# 555_blinker_led.net
KiCad netlist of a schematic drawn in EasyEDA
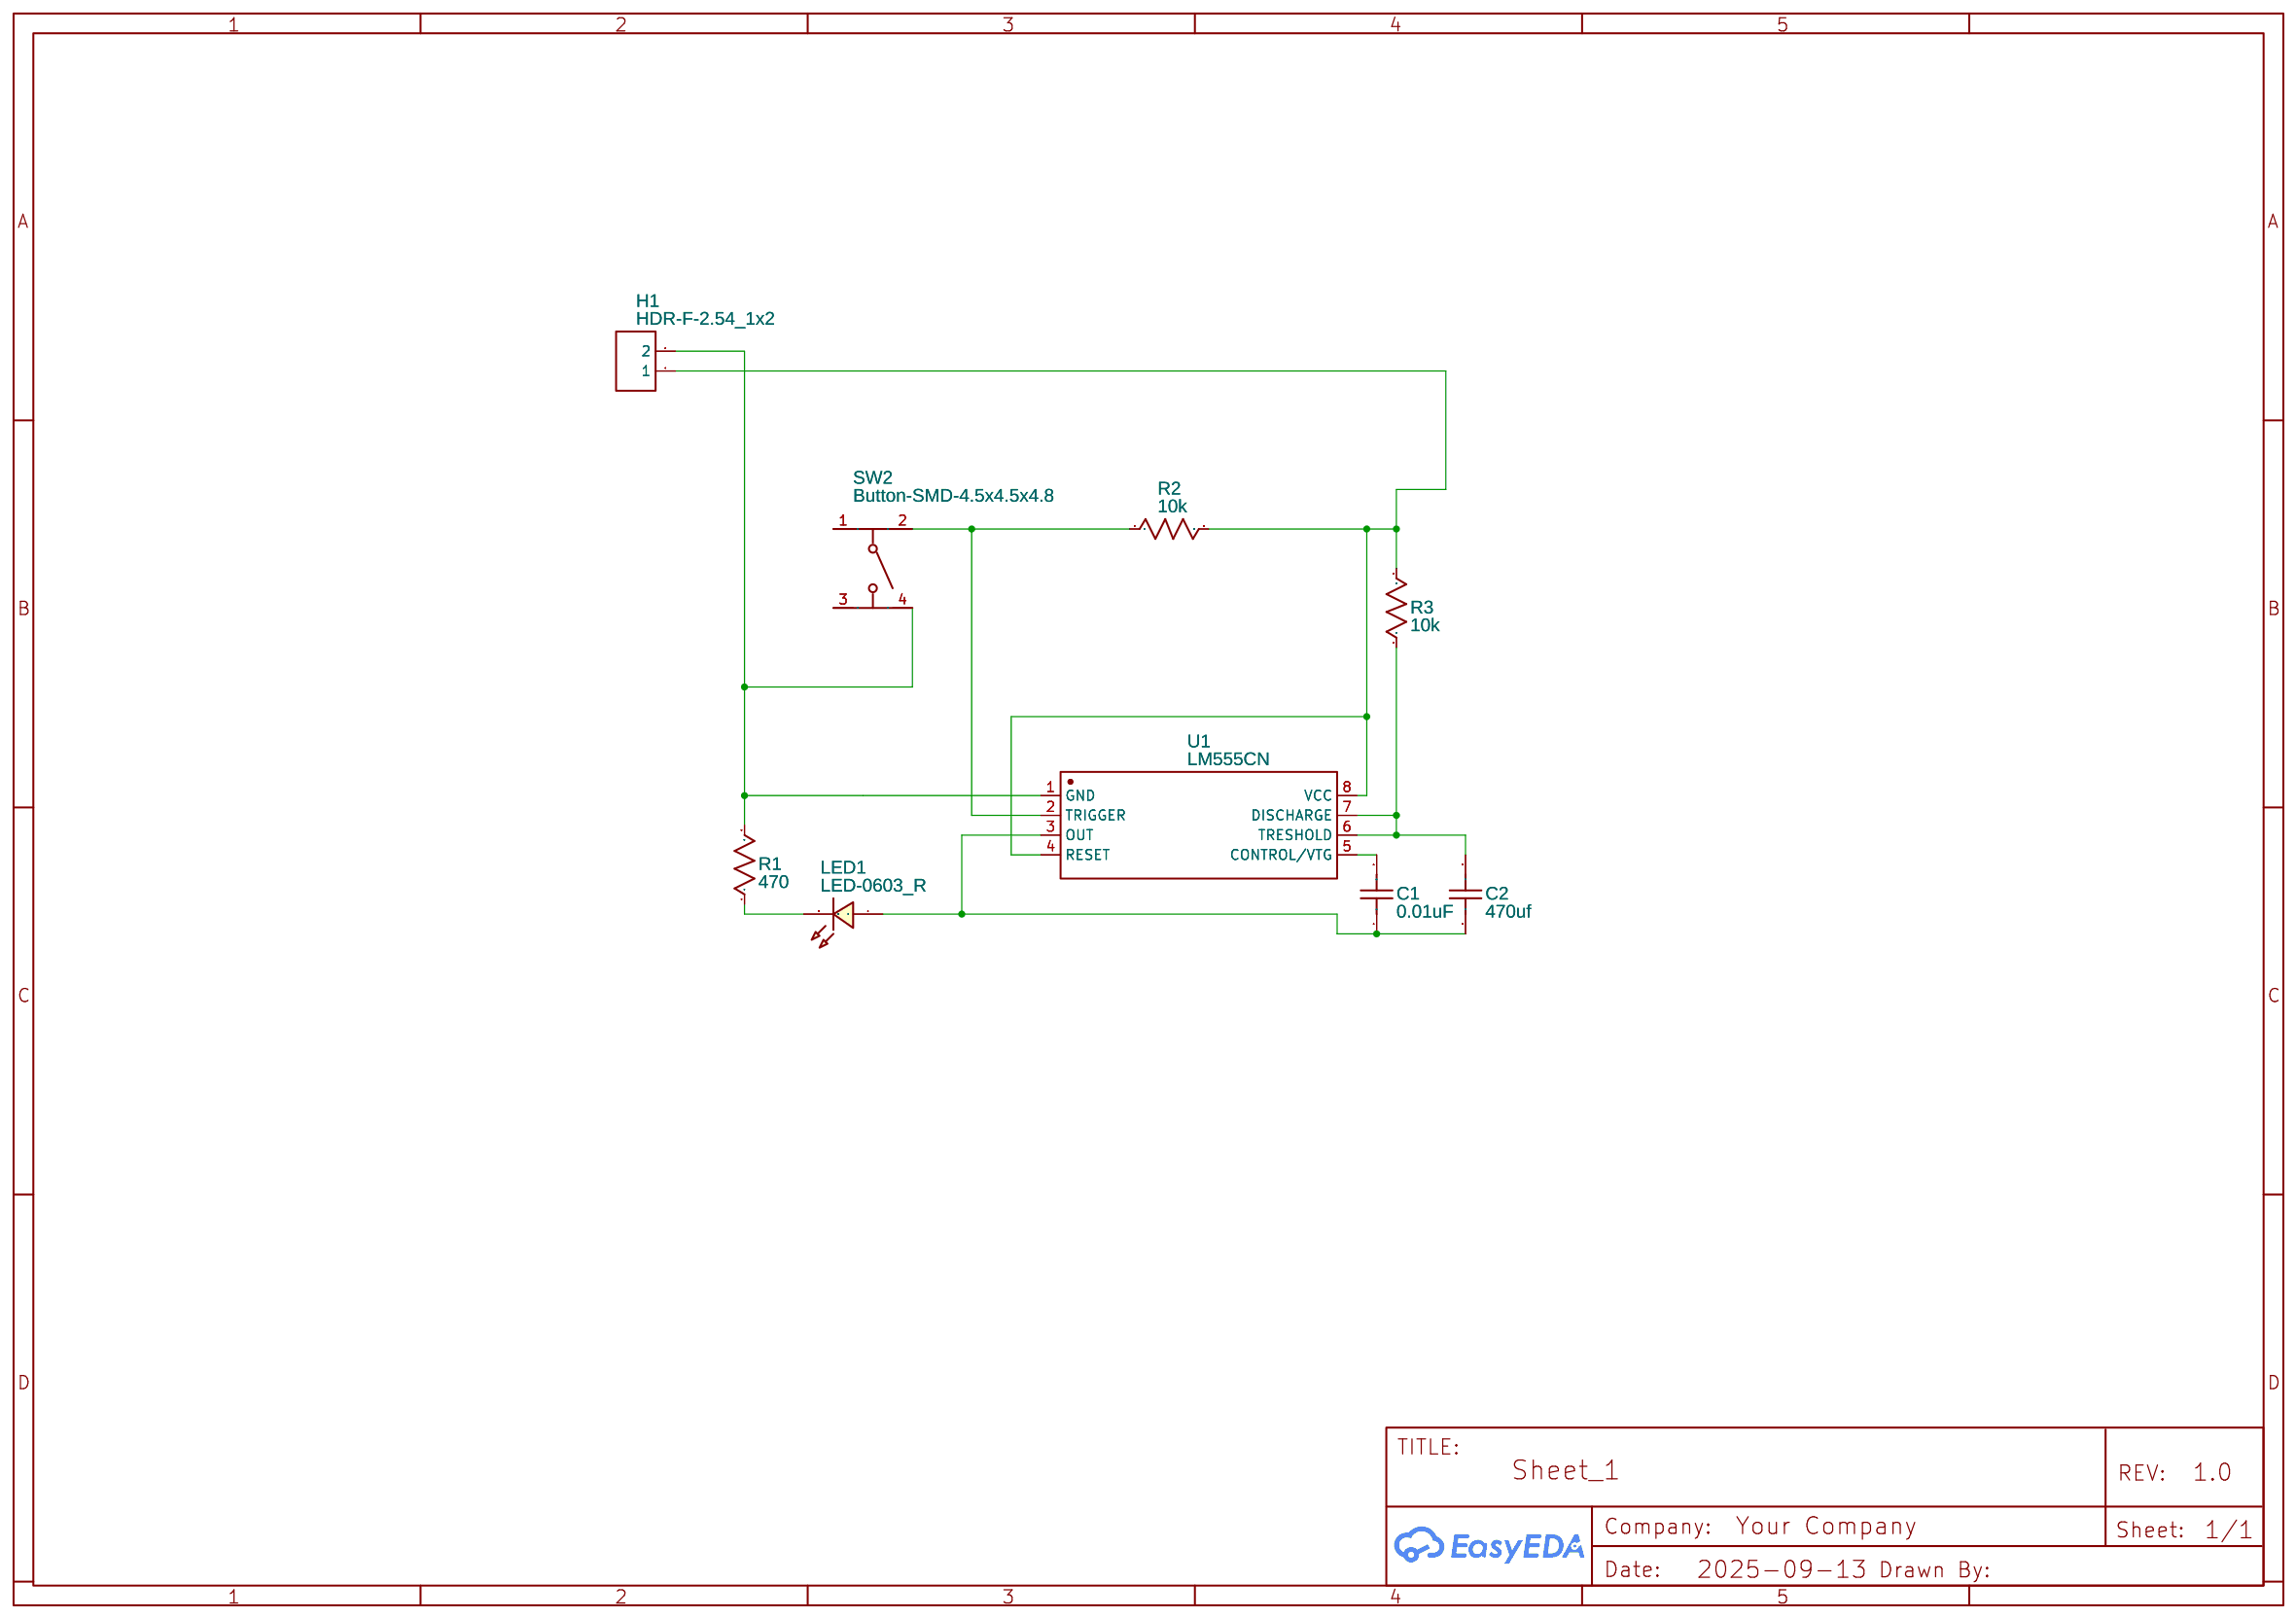
[diagram p0: schematic sheet]

(export (version "E")
  (design (tool "Eeschema 10.0.6"))
  (components
    (comp (ref "C1") (value "0.01uF") (libsource (lib "") (part "C_0603_US")))
    (comp (ref "C2") (value "470uf") (libsource (lib "") (part "C_0603_US")))
    (comp (ref "H1") (value "HDR-F-2.54_1x2") (libsource (lib "") (part "HDR-F-2.54_1x2")))
    (comp (ref "LED1")
      (value "LED-0603_R")
      (fields
        (field (name "Manufacturer Part") "19-217/R6C-AL1M2VY/3T")
        (field (name "Manufacturer") "EVERLIGHT(台湾亿光)")
      )
      (libsource (lib "") (part "LED-0603_R"))
    )
    (comp (ref "R1") (value "470") (libsource (lib "") (part "R_0603_US")))
    (comp (ref "R2") (value "10k") (libsource (lib "") (part "R_0603_US_1")))
    (comp (ref "R3") (value "10k") (libsource (lib "") (part "R_0603_US")))
    (comp (ref "SW2")
      (value "Button-SMD-4.5x4.5x4.8")
      (fields
        (field (name "Manufacturer Part") "4.5*4.5*4.8 Plastic head,260G, 0.25mm,SMD")
        (field (name "Manufacturer") "BBJ")
      )
      (libsource (lib "") (part "Button-SMD-4.5x4.5x4.8"))
    )
    (comp (ref "U1")
      (value "LM555CN")
      (fields (field (name "Manufacturer") "onsemi(安森美)"))
      (libsource (lib "") (part "LM555CN"))
    )
  )
  (nets
    (net (code "1") (name "Net-(LED1-Pad2)") (class "Default")
      (node (ref "LED1") (pin "2") (pinfunction "2_2") (pintype "unspecified"))
      (node (ref "R1") (pin "1") (pinfunction "1_1") (pintype "unspecified"))
    )
    (net (code "2") (name "Net-(U1-CONTROL{slash}VTG)") (class "Default")
      (node (ref "C1") (pin "2") (pinfunction "2_2") (pintype "unspecified"))
      (node (ref "U1") (pin "5") (pinfunction "CONTROL/VTG_5") (pintype "unspecified"))
    )
    (net (code "3") (name "Net-(U1-DISCHARGE)") (class "Default")
      (node (ref "C2") (pin "2") (pinfunction "2_2") (pintype "unspecified"))
      (node (ref "R3") (pin "1") (pinfunction "1_1") (pintype "unspecified"))
      (node (ref "U1") (pin "6") (pinfunction "TRESHOLD_6") (pintype "unspecified"))
      (node (ref "U1") (pin "7") (pinfunction "DISCHARGE_7") (pintype "unspecified"))
    )
    (net (code "4") (name "Net-(U1-GND)") (class "Default")
      (node (ref "H1") (pin "2") (pinfunction "2_2") (pintype "input"))
      (node (ref "R1") (pin "2") (pinfunction "2_2") (pintype "unspecified"))
      (node (ref "SW2") (pin "4") (pinfunction "4_4") (pintype "unspecified"))
      (node (ref "U1") (pin "1") (pinfunction "GND_1") (pintype "unspecified"))
    )
    (net (code "5") (name "Net-(U1-OUT)") (class "Default")
      (node (ref "C1") (pin "1") (pinfunction "1_1") (pintype "unspecified"))
      (node (ref "C2") (pin "1") (pinfunction "1_1") (pintype "unspecified"))
      (node (ref "LED1") (pin "1") (pinfunction "1_1") (pintype "unspecified"))
      (node (ref "U1") (pin "3") (pinfunction "OUT_3") (pintype "unspecified"))
    )
    (net (code "6") (name "Net-(U1-RESET)") (class "Default")
      (node (ref "H1") (pin "1") (pinfunction "1_1") (pintype "input"))
      (node (ref "R2") (pin "2") (pinfunction "2_2") (pintype "unspecified"))
      (node (ref "R3") (pin "2") (pinfunction "2_2") (pintype "unspecified"))
      (node (ref "U1") (pin "4") (pinfunction "RESET_4") (pintype "unspecified"))
      (node (ref "U1") (pin "8") (pinfunction "VCC_8") (pintype "unspecified"))
    )
    (net (code "7") (name "Net-(U1-TRIGGER)") (class "Default")
      (node (ref "R2") (pin "1") (pinfunction "1_1") (pintype "unspecified"))
      (node (ref "SW2") (pin "2") (pinfunction "2_2") (pintype "unspecified"))
      (node (ref "U1") (pin "2") (pinfunction "TRIGGER_2") (pintype "unspecified"))
    )
    (net (code "8") (name "unconnected-(SW2-Pad1)") (class "Default")
      (node (ref "SW2") (pin "1") (pinfunction "1_1") (pintype "unspecified"))
    )
    (net (code "9") (name "unconnected-(SW2-Pad3)") (class "Default")
      (node (ref "SW2") (pin "3") (pinfunction "3_3") (pintype "unspecified"))
    )
  )
)
